# RFID_Breakout.net
KiCad netlist of a schematic drawn in EAGLE
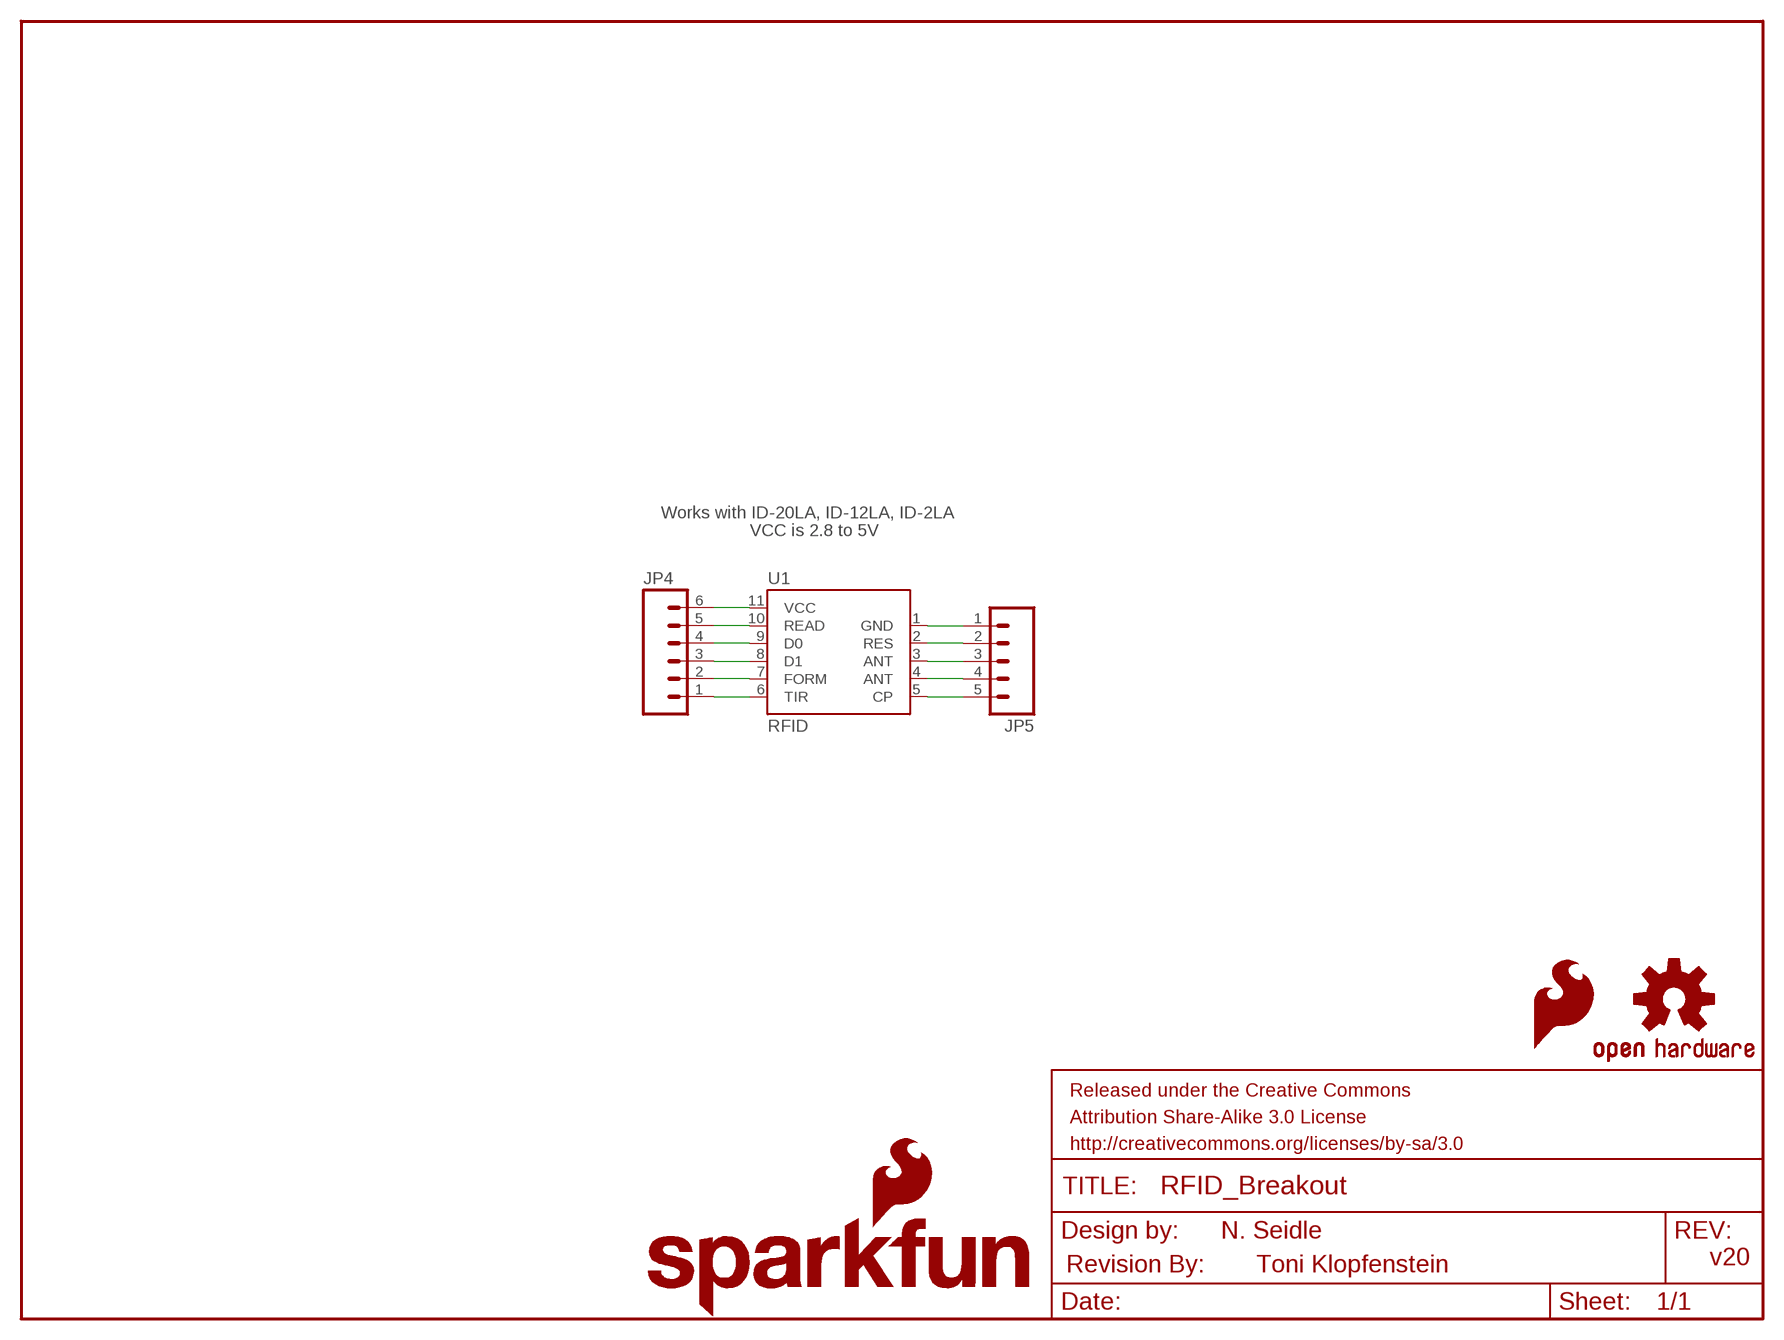
[diagram p0: schematic, sheet 1]

(export (version "E")
  (design (tool "Eeschema 10.0.6"))
  (components
    (comp (ref "FRAME1")
      (value "FRAME-LETTER")
      (footprint "eagle-import:CREATIVE_COMMONS")
      (libsource (lib "eagle-import") (part "FRAME-LETTER"))
    )
    (comp (ref "JP4")
      (value "M06SIP")
      (footprint "eagle-import:1X06")
      (libsource (lib "eagle-import") (part "M06SIP"))
    )
    (comp (ref "JP5")
      (value "M05PTH")
      (footprint "eagle-import:1X05")
      (libsource (lib "eagle-import") (part "M05PTH"))
    )
    (comp (ref "LOGO1")
      (value "SFE_LOGO_FLAME.1_INCH")
      (footprint "eagle-import:SFE_LOGO_FLAME_.1")
      (libsource (lib "eagle-import") (part "SFE_LOGO_FLAME.1_INCH"))
    )
    (comp (ref "LOGO2")
      (value "SFE_LOGO_NAME_FLAME.1_INCH")
      (footprint "eagle-import:SFE_LOGO_NAME_FLAME_.1")
      (libsource (lib "eagle-import") (part "SFE_LOGO_NAME_FLAME.1_INCH"))
    )
    (comp (ref "LOGO3")
      (value "OSHW-LOGOS")
      (footprint "eagle-import:OSHW-LOGO-S")
      (libsource (lib "eagle-import") (part "OSHW-LOGOS"))
    )
    (comp (ref "U$1")
      (value "REVISION")
      (footprint "eagle-import:REVISION")
      (libsource (lib "eagle-import") (part "REVISION"))
    )
    (comp (ref "U1")
      (value "RFID")
      (footprint "eagle-import:ID_PACKAGE")
      (libsource (lib "eagle-import") (part "RFIDALL"))
    )
  )
  (nets
    (net (code "1") (name "Net-(JP5-Pad3)") (class "Default")
      (node (ref "JP5") (pin "3") (pinfunction "3_3") (pintype "passive"))
      (node (ref "U1") (pin "3") (pinfunction "ANT_3") (pintype "bidirectional"))
    )
    (net (code "2") (name "Net-(JP5-Pad4)") (class "Default")
      (node (ref "JP5") (pin "4") (pinfunction "4_4") (pintype "passive"))
      (node (ref "U1") (pin "4") (pinfunction "ANT_4") (pintype "bidirectional"))
    )
    (net (code "3") (name "Net-(U1-CP)") (class "Default")
      (node (ref "JP5") (pin "5") (pinfunction "5_5") (pintype "passive"))
      (node (ref "U1") (pin "5") (pinfunction "CP_5") (pintype "bidirectional"))
    )
    (net (code "4") (name "Net-(U1-D0)") (class "Default")
      (node (ref "JP4") (pin "4") (pinfunction "4_4") (pintype "passive"))
      (node (ref "U1") (pin "9") (pinfunction "D0_9") (pintype "bidirectional"))
    )
    (net (code "5") (name "Net-(U1-D1)") (class "Default")
      (node (ref "JP4") (pin "3") (pinfunction "3_3") (pintype "passive"))
      (node (ref "U1") (pin "8") (pinfunction "D1_8") (pintype "bidirectional"))
    )
    (net (code "6") (name "Net-(U1-FORM)") (class "Default")
      (node (ref "JP4") (pin "2") (pinfunction "2_2") (pintype "passive"))
      (node (ref "U1") (pin "7") (pinfunction "FORM_7") (pintype "bidirectional"))
    )
    (net (code "7") (name "Net-(U1-GND)") (class "Default")
      (node (ref "JP5") (pin "1") (pinfunction "1_1") (pintype "passive"))
      (node (ref "U1") (pin "1") (pinfunction "GND_1") (pintype "bidirectional"))
    )
    (net (code "8") (name "Net-(U1-READ)") (class "Default")
      (node (ref "JP4") (pin "5") (pinfunction "5_5") (pintype "passive"))
      (node (ref "U1") (pin "10") (pinfunction "READ_10") (pintype "bidirectional"))
    )
    (net (code "9") (name "Net-(U1-RES)") (class "Default")
      (node (ref "JP5") (pin "2") (pinfunction "2_2") (pintype "passive"))
      (node (ref "U1") (pin "2") (pinfunction "RES_2") (pintype "bidirectional"))
    )
    (net (code "10") (name "Net-(U1-TIR)") (class "Default")
      (node (ref "JP4") (pin "1") (pinfunction "1_1") (pintype "passive"))
      (node (ref "U1") (pin "6") (pinfunction "TIR_6") (pintype "bidirectional"))
    )
    (net (code "11") (name "Net-(U1-VCC)") (class "Default")
      (node (ref "JP4") (pin "6") (pinfunction "6_6") (pintype "passive"))
      (node (ref "U1") (pin "11") (pinfunction "VCC_11") (pintype "bidirectional"))
    )
  )
)
